# soldering.net
KiCad netlist of a schematic drawn in Altium Designer
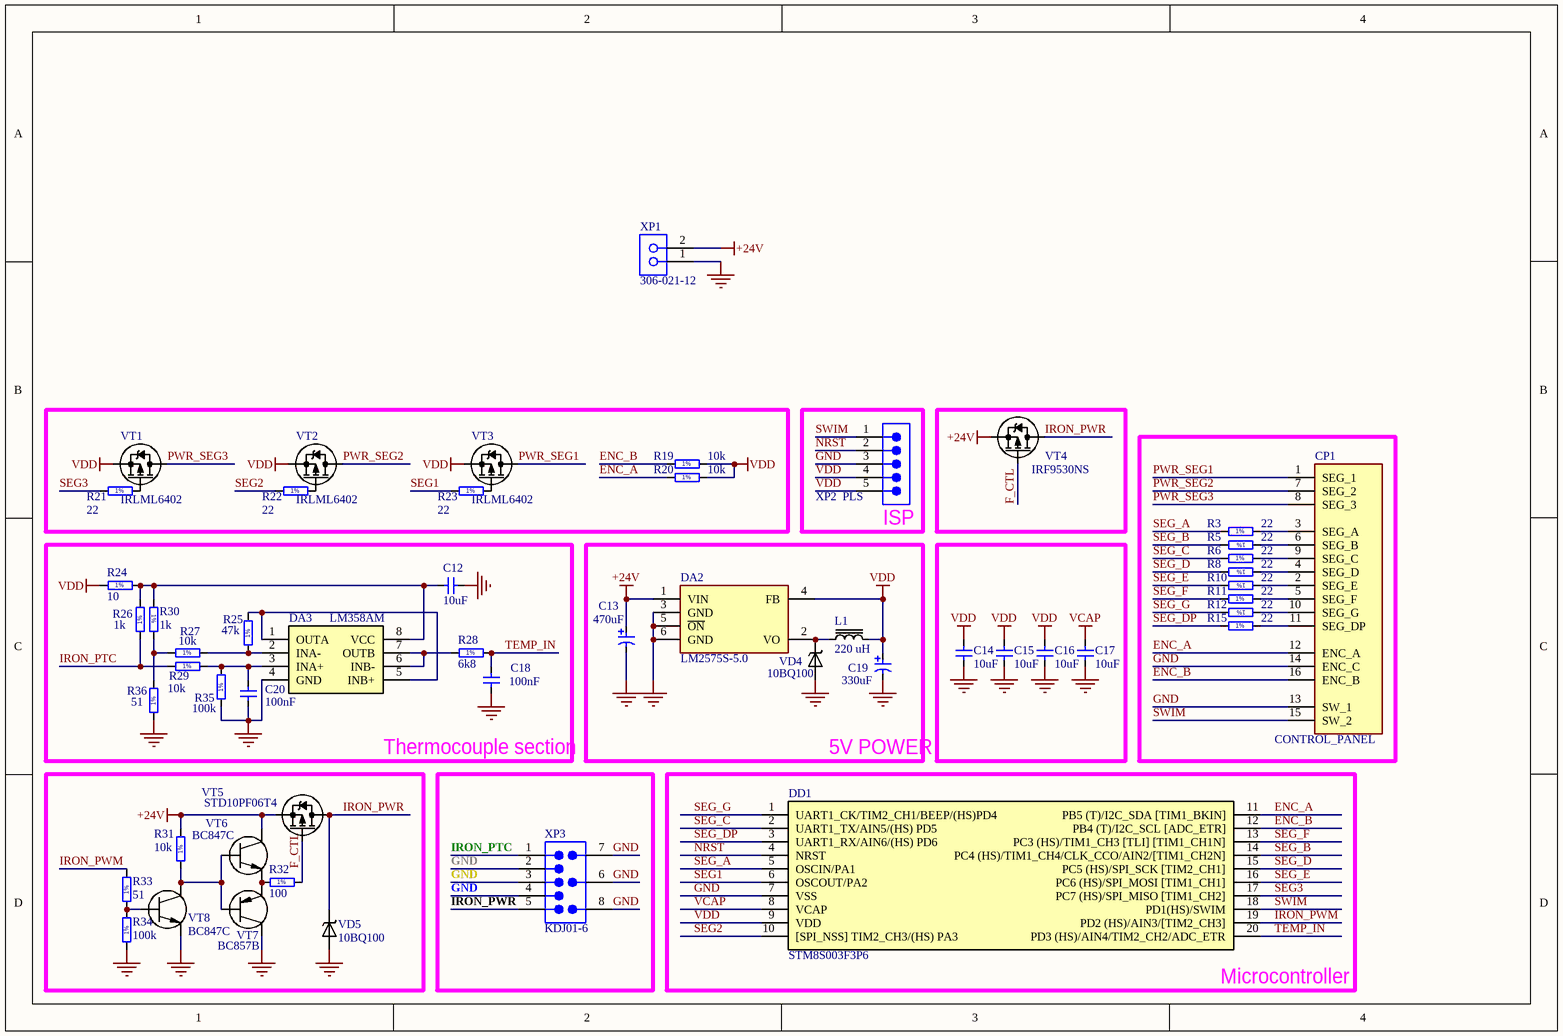
[diagram p0: soldering.SchDoc]

(export (version "E")
  (design (tool "Eeschema 10.0.6"))
  (components
    (comp (ref "C12")
      (value "10uF")
      (footprint "CAP0805R")
      (description "SMD 0805 Capacitor")
      (fields
        (field (name "PART NUMBER") "CC0805_10UF_10V_10%_X7R")
        (field (name "VOLTAGE") "10V")
        (field (name "AUTHOR") "I. Kuznetsov")
      )
      (libsource (lib "Capacitor") (part "CAP_NON_POLAR"))
    )
    (comp (ref "C13")
      (value "470uF")
      (footprint "CAP_EL_10_19_VERT")
      (fields (field (name "PART NUMBER") "SH050M0470B5S-1019 (VERT MOUNTED)") (field (name "VOLTAGE") "50V"))
      (libsource (lib "Capacitor") (part "CAP_POLAR"))
    )
    (comp (ref "C14")
      (value "10uF")
      (footprint "CAP0805R")
      (description "SMD 0805 Capacitor")
      (fields
        (field (name "PART NUMBER") "CC0805_10UF_10V_10%_X7R")
        (field (name "VOLTAGE") "10V")
        (field (name "AUTHOR") "I. Kuznetsov")
      )
      (libsource (lib "Capacitor") (part "CAP_NON_POLAR"))
    )
    (comp (ref "C15")
      (value "10uF")
      (footprint "CAP0805R")
      (description "SMD 0805 Capacitor")
      (fields
        (field (name "PART NUMBER") "CC0805_10UF_10V_10%_X7R")
        (field (name "VOLTAGE") "10V")
        (field (name "AUTHOR") "I. Kuznetsov")
      )
      (libsource (lib "Capacitor") (part "CAP_NON_POLAR"))
    )
    (comp (ref "C16")
      (value "10uF")
      (footprint "CAP0805R")
      (description "SMD 0805 Capacitor")
      (fields
        (field (name "PART NUMBER") "CC0805_10UF_10V_10%_X7R")
        (field (name "VOLTAGE") "10V")
        (field (name "AUTHOR") "I. Kuznetsov")
      )
      (libsource (lib "Capacitor") (part "CAP_NON_POLAR"))
    )
    (comp (ref "C17")
      (value "10uF")
      (footprint "CAP0805R")
      (description "SMD 0805 Capacitor")
      (fields
        (field (name "PART NUMBER") "CC0805_10UF_10V_10%_X7R")
        (field (name "VOLTAGE") "10V")
        (field (name "AUTHOR") "I. Kuznetsov")
      )
      (libsource (lib "Capacitor") (part "CAP_NON_POLAR"))
    )
    (comp (ref "C18")
      (value "100nF")
      (footprint "CAP0805R")
      (description "SMD 0805 Capacitor")
      (fields
        (field (name "PART NUMBER") "CC0805_100NF_50V_10%_X7R")
        (field (name "VOLTAGE") "50V")
        (field (name "AUTHOR") "I. Kuznetsov")
      )
      (libsource (lib "Capacitor") (part "CAP_NON_POLAR"))
    )
    (comp (ref "C19")
      (value "330uF")
      (footprint "TAN_D")
      (fields (field (name "PART NUMBER") "T495D337M010AHE100") (field (name "VOLTAGE") "10V"))
      (libsource (lib "Capacitor") (part "CAP_POLAR"))
    )
    (comp (ref "C20")
      (value "100nF")
      (footprint "CAP0805R")
      (description "SMD 0805 Capacitor")
      (fields
        (field (name "PART NUMBER") "CC0805_100NF_50V_10%_X7R")
        (field (name "VOLTAGE") "50V")
        (field (name "AUTHOR") "I. Kuznetsov")
      )
      (libsource (lib "Capacitor") (part "CAP_NON_POLAR"))
    )
    (comp (ref "CP1")
      (value "CONTROL_PANEL")
      (footprint "CONTROL_PANEL")
      (libsource (lib "soldering") (part "CONTROL_PANEL"))
    )
    (comp (ref "DA2")
      (value "LM2575S-5.0")
      (footprint "TO-263-5")
      (fields (field (name "MANUFACTURER") "TI") (field (name "AUTHOR") "I. Kuznetsov"))
      (libsource (lib "IC And Semiconductor") (part "LM2575S"))
    )
    (comp (ref "DA3")
      (value "OP Amp")
      (footprint "SOP8")
      (fields (field (name "PARTNUMBER") "LM358AM"))
      (libsource (lib "tonometr") (part "LM358AM"))
    )
    (comp (ref "DD1")
      (value "8 Bit MCU")
      (footprint "TSSOP20")
      (description "8 Bit MCU (STmicroelectronics)")
      (fields (field (name "PARTNUMBER") "STM8S003F3P6"))
      (libsource (lib "soldering") (part "STM8S003F3P6"))
    )
    (comp (ref "L1")
      (value "220 uH")
      (footprint "SL1016")
      (fields (field (name "PART NUMBER") "SL1016T-4R7K-B-N") (field (name "TOLERANCE") "± 10%"))
      (libsource (lib "Transformer") (part "Core_Inductor"))
    )
    (comp (ref "R3")
      (value "22")
      (footprint "RES0805R")
      (fields
        (field (name "PART NUMBER") "R0805_22R_1%_0.125W_100PPM")
        (field (name "POWER") "0.125W")
        (field (name "TOLERANCE") "±1%")
        (field (name "AUTHOR") "CERN DEM JLC")
      )
      (libsource (lib "Resistor") (part "Resistor - 1%"))
    )
    (comp (ref "R5")
      (value "22")
      (footprint "RES0805R")
      (fields
        (field (name "PART NUMBER") "R0805_22R_1%_0.125W_100PPM")
        (field (name "POWER") "0.125W")
        (field (name "TOLERANCE") "±1%")
        (field (name "AUTHOR") "CERN DEM JLC")
      )
      (libsource (lib "Resistor") (part "Resistor - 1%"))
    )
    (comp (ref "R6")
      (value "22")
      (footprint "RES0805R")
      (fields
        (field (name "PART NUMBER") "R0805_22R_1%_0.125W_100PPM")
        (field (name "POWER") "0.125W")
        (field (name "TOLERANCE") "±1%")
        (field (name "AUTHOR") "CERN DEM JLC")
      )
      (libsource (lib "Resistor") (part "Resistor - 1%"))
    )
    (comp (ref "R8")
      (value "22")
      (footprint "RES0805R")
      (fields
        (field (name "PART NUMBER") "R0805_22R_1%_0.125W_100PPM")
        (field (name "POWER") "0.125W")
        (field (name "TOLERANCE") "±1%")
        (field (name "AUTHOR") "CERN DEM JLC")
      )
      (libsource (lib "Resistor") (part "Resistor - 1%"))
    )
    (comp (ref "R10")
      (value "22")
      (footprint "RES0805R")
      (fields
        (field (name "PART NUMBER") "R0805_22R_1%_0.125W_100PPM")
        (field (name "POWER") "0.125W")
        (field (name "TOLERANCE") "±1%")
        (field (name "AUTHOR") "CERN DEM JLC")
      )
      (libsource (lib "Resistor") (part "Resistor - 1%"))
    )
    (comp (ref "R11")
      (value "22")
      (footprint "RES0805R")
      (fields
        (field (name "PART NUMBER") "R0805_22R_1%_0.125W_100PPM")
        (field (name "POWER") "0.125W")
        (field (name "TOLERANCE") "±1%")
        (field (name "AUTHOR") "CERN DEM JLC")
      )
      (libsource (lib "Resistor") (part "Resistor - 1%"))
    )
    (comp (ref "R12")
      (value "22")
      (footprint "RES0805R")
      (fields
        (field (name "PART NUMBER") "R0805_22R_1%_0.125W_100PPM")
        (field (name "POWER") "0.125W")
        (field (name "TOLERANCE") "±1%")
        (field (name "AUTHOR") "CERN DEM JLC")
      )
      (libsource (lib "Resistor") (part "Resistor - 1%"))
    )
    (comp (ref "R15")
      (value "22")
      (footprint "RES0805R")
      (fields
        (field (name "PART NUMBER") "R0805_22R_1%_0.125W_100PPM")
        (field (name "POWER") "0.125W")
        (field (name "TOLERANCE") "±1%")
        (field (name "AUTHOR") "CERN DEM JLC")
      )
      (libsource (lib "Resistor") (part "Resistor - 1%"))
    )
    (comp (ref "R19")
      (value "10k")
      (footprint "RES0805R")
      (fields
        (field (name "PART NUMBER") "R0805_10K_1%_0.125W_100PPM")
        (field (name "POWER") "0.125W")
        (field (name "TOLERANCE") "±1%")
        (field (name "AUTHOR") "CERN DEM JLC")
      )
      (libsource (lib "Resistor") (part "Resistor - 1%"))
    )
    (comp (ref "R20")
      (value "10k")
      (footprint "RES0805R")
      (fields
        (field (name "PART NUMBER") "R0805_10K_1%_0.125W_100PPM")
        (field (name "POWER") "0.125W")
        (field (name "TOLERANCE") "±1%")
        (field (name "AUTHOR") "CERN DEM JLC")
      )
      (libsource (lib "Resistor") (part "Resistor - 1%"))
    )
    (comp (ref "R21")
      (value "22")
      (footprint "RES0805R")
      (fields
        (field (name "PART NUMBER") "R0805_22R_1%_0.125W_100PPM")
        (field (name "POWER") "0.125W")
        (field (name "TOLERANCE") "±1%")
        (field (name "AUTHOR") "CERN DEM JLC")
      )
      (libsource (lib "Resistor") (part "Resistor - 1%"))
    )
    (comp (ref "R22")
      (value "22")
      (footprint "RES0805R")
      (fields
        (field (name "PART NUMBER") "R0805_22R_1%_0.125W_100PPM")
        (field (name "POWER") "0.125W")
        (field (name "TOLERANCE") "±1%")
        (field (name "AUTHOR") "CERN DEM JLC")
      )
      (libsource (lib "Resistor") (part "Resistor - 1%"))
    )
    (comp (ref "R23")
      (value "22")
      (footprint "RES0805R")
      (fields
        (field (name "PART NUMBER") "R0805_22R_1%_0.125W_100PPM")
        (field (name "POWER") "0.125W")
        (field (name "TOLERANCE") "±1%")
        (field (name "AUTHOR") "CERN DEM JLC")
      )
      (libsource (lib "Resistor") (part "Resistor - 1%"))
    )
    (comp (ref "R24")
      (value "10")
      (footprint "RES0805R")
      (fields
        (field (name "PART NUMBER") "R0805_10R_1%_0.125W_200PPM")
        (field (name "POWER") "0.125W")
        (field (name "TOLERANCE") "±1%")
        (field (name "AUTHOR") "CERN DEM JLC")
      )
      (libsource (lib "Resistor") (part "Resistor - 1%"))
    )
    (comp (ref "R25")
      (value "47k")
      (footprint "RES0805R")
      (fields
        (field (name "PART NUMBER") "R0805_47K_1%_0.125W_100PPM")
        (field (name "POWER") "0.125W")
        (field (name "TOLERANCE") "±1%")
        (field (name "AUTHOR") "CERN DEM JLC")
      )
      (libsource (lib "Resistor") (part "Resistor - 1%"))
    )
    (comp (ref "R26")
      (value "1k")
      (footprint "RES0805R")
      (fields
        (field (name "PART NUMBER") "R0805_1K_1%_0.125W_100PPM")
        (field (name "POWER") "0.125W")
        (field (name "TOLERANCE") "±1%")
        (field (name "AUTHOR") "CERN DEM JLC")
      )
      (libsource (lib "Resistor") (part "Resistor - 1%"))
    )
    (comp (ref "R27")
      (value "10k")
      (footprint "RES0805R")
      (fields
        (field (name "PART NUMBER") "R0805_10K_1%_0.125W_100PPM")
        (field (name "POWER") "0.125W")
        (field (name "TOLERANCE") "±1%")
        (field (name "AUTHOR") "CERN DEM JLC")
      )
      (libsource (lib "Resistor") (part "Resistor - 1%"))
    )
    (comp (ref "R28")
      (value "6k8")
      (footprint "RES0805R")
      (fields
        (field (name "PART NUMBER") "R0805_6K8_1%_0.125W_100PPM")
        (field (name "POWER") "0.125W")
        (field (name "TOLERANCE") "±1%")
        (field (name "AUTHOR") "CERN DEM JLC")
      )
      (libsource (lib "Resistor") (part "Resistor - 1%"))
    )
    (comp (ref "R29")
      (value "10k")
      (footprint "RES0805R")
      (fields
        (field (name "PART NUMBER") "R0805_10K_1%_0.125W_100PPM")
        (field (name "POWER") "0.125W")
        (field (name "TOLERANCE") "±1%")
        (field (name "AUTHOR") "CERN DEM JLC")
      )
      (libsource (lib "Resistor") (part "Resistor - 1%"))
    )
    (comp (ref "R30")
      (value "1k")
      (footprint "RES0805R")
      (fields
        (field (name "PART NUMBER") "R0805_1K_1%_0.125W_100PPM")
        (field (name "POWER") "0.125W")
        (field (name "TOLERANCE") "±1%")
        (field (name "AUTHOR") "CERN DEM JLC")
      )
      (libsource (lib "Resistor") (part "Resistor - 1%"))
    )
    (comp (ref "R31")
      (value "10k")
      (footprint "RES0805R")
      (fields
        (field (name "PART NUMBER") "R0805_10K_1%_0.125W_100PPM")
        (field (name "POWER") "0.125W")
        (field (name "TOLERANCE") "±1%")
        (field (name "AUTHOR") "CERN DEM JLC")
      )
      (libsource (lib "Resistor") (part "Resistor - 1%"))
    )
    (comp (ref "R32")
      (value "100")
      (footprint "RES0805R")
      (fields
        (field (name "PART NUMBER") "R0805_100R_1%_0.125W_100PPM")
        (field (name "POWER") "0.125W")
        (field (name "TOLERANCE") "±1%")
        (field (name "AUTHOR") "CERN DEM JLC")
      )
      (libsource (lib "Resistor") (part "Resistor - 1%"))
    )
    (comp (ref "R33")
      (value "51")
      (footprint "RES0805R")
      (fields
        (field (name "PART NUMBER") "R0805_51R_1%_0.125W_100PPM")
        (field (name "POWER") "0.125W")
        (field (name "TOLERANCE") "±1%")
        (field (name "AUTHOR") "CERN DEM JLC")
      )
      (libsource (lib "Resistor") (part "Resistor - 1%"))
    )
    (comp (ref "R34")
      (value "100k")
      (footprint "RES0805R")
      (fields
        (field (name "PART NUMBER") "R0805_100K_1%_0.125W_100PPM")
        (field (name "POWER") "0.125W")
        (field (name "TOLERANCE") "±1%")
        (field (name "AUTHOR") "CERN DEM JLC")
      )
      (libsource (lib "Resistor") (part "Resistor - 1%"))
    )
    (comp (ref "R35")
      (value "100k")
      (footprint "RES0805R")
      (fields
        (field (name "PART NUMBER") "R0805_100K_1%_0.125W_100PPM")
        (field (name "MANUFACTURER") "GENERIC")
        (field (name "MANUFACTURER1 PART NUMBER") "NRC10F1003TRF")
        (field (name "AUTHOR") "CERN DEM JLC")
      )
      (libsource (lib "Resistor") (part "Resistor - 1%"))
    )
    (comp (ref "R36")
      (value "51")
      (footprint "RES0805R")
      (fields
        (field (name "PART NUMBER") "R0805_51R_1%_0.125W_100PPM")
        (field (name "POWER") "0.125W")
        (field (name "TOLERANCE") "±1%")
        (field (name "AUTHOR") "CERN DEM JLC")
      )
      (libsource (lib "Resistor") (part "Resistor - 1%"))
    )
    (comp (ref "VD4")
      (value "10BQ100")
      (footprint "DO-214AA")
      (fields (field (name "MANUFACTURER") "IR") (field (name "AUTHOR") "I. Kuznetsov"))
      (libsource (lib "IC And Semiconductor") (part "Diode - Schottky"))
    )
    (comp (ref "VD5")
      (value "10BQ100")
      (footprint "DO-214AA")
      (fields (field (name "MANUFACTURER") "IR") (field (name "AUTHOR") "I. Kuznetsov"))
      (libsource (lib "IC And Semiconductor") (part "Diode - Schottky"))
    )
    (comp (ref "VT1")
      (value "IRLML6402")
      (footprint "SOT23")
      (fields (field (name "AUTHOR") "I. Kuznetsov"))
      (libsource (lib "IC And Semiconductor") (part "P_CH_MOSFET"))
    )
    (comp (ref "VT2")
      (value "IRLML6402")
      (footprint "SOT23")
      (fields (field (name "AUTHOR") "I. Kuznetsov"))
      (libsource (lib "IC And Semiconductor") (part "P_CH_MOSFET"))
    )
    (comp (ref "VT3")
      (value "IRLML6402")
      (footprint "SOT23")
      (fields (field (name "AUTHOR") "I. Kuznetsov"))
      (libsource (lib "IC And Semiconductor") (part "P_CH_MOSFET"))
    )
    (comp (ref "VT4")
      (value "IRF9530NS")
      (footprint "D2PAK")
      (libsource (lib "IC And Semiconductor") (part "P_CH_MOSFET"))
    )
    (comp (ref "VT5")
      (value "STD10PF06T4")
      (footprint "DPAK")
      (fields (field (name "AUTHOR") "I. Kuznetsov"))
      (libsource (lib "IC And Semiconductor") (part "P_CH_MOSFET"))
    )
    (comp (ref "VT6")
      (value "BC847C")
      (footprint "SOT23")
      (fields (field (name "AUTHOR") "I. Kuznetsov"))
      (libsource (lib "IC And Semiconductor") (part "NPN_BIPOLAR_SOT23"))
    )
    (comp (ref "VT7")
      (value "BC857B")
      (footprint "SOT23")
      (fields (field (name "AUTHOR") "I. Kuznetsov"))
      (libsource (lib "IC And Semiconductor") (part "PNP_BIPOLAR"))
    )
    (comp (ref "VT8")
      (value "BC847C")
      (footprint "SOT23")
      (fields (field (name "AUTHOR") "I. Kuznetsov"))
      (libsource (lib "IC And Semiconductor") (part "NPN_BIPOLAR_SOT23"))
    )
    (comp (ref "XP1")
      (value "306-021-12")
      (footprint "306-021-12")
      (libsource (lib "Connector") (part "CN_02S_1W"))
    )
    (comp (ref "XP2")
      (value "PLS")
      (footprint "PLS-05")
      (fields (field (name "PART NUMBER") "PLS-05") (field (name "MANUFACTURER") "AUK"))
      (libsource (lib "Connector") (part "CN_05P_1W"))
    )
    (comp (ref "XP3") (value "KDJ01-6") (footprint "KDJ01-6") (libsource (lib "Connector") (part "KDJ01-6")))
  )
  (nets
    (net (code "1") (name "+24V") (class "Default")
      (node (ref "C13") (pin "2") (pinfunction "2_2") (pintype "passive"))
      (node (ref "DA2") (pin "1") (pinfunction "VIN_1") (pintype "passive"))
      (node (ref "R31") (pin "2") (pinfunction "2_2") (pintype "passive"))
      (node (ref "VT4") (pin "2") (pinfunction "S_2") (pintype "passive"))
      (node (ref "VT5") (pin "2") (pinfunction "S_2") (pintype "passive"))
      (node (ref "VT6") (pin "3") (pinfunction "C_3") (pintype "passive"))
      (node (ref "XP1") (pin "2") (pinfunction "2_2") (pintype "passive"))
    )
    (net (code "2") (name "/ENC_A") (class "Default")
      (node (ref "CP1") (pin "12") (pinfunction "ENC_A_12") (pintype "passive"))
      (node (ref "DD1") (pin "11") (pinfunction "PB5_(T)/I2C_SDA_[TIM1_BKIN]_11") (pintype "passive"))
      (node (ref "R20") (pin "1") (pinfunction "1_1") (pintype "passive"))
    )
    (net (code "3") (name "/ENC_B") (class "Default")
      (node (ref "CP1") (pin "16") (pinfunction "ENC_B_16") (pintype "passive"))
      (node (ref "DD1") (pin "12") (pinfunction "PB4_(T)/I2C_SCL_[ADC_ETR]_12") (pintype "passive"))
      (node (ref "R19") (pin "1") (pinfunction "1_1") (pintype "passive"))
    )
    (net (code "4") (name "/F_CTL") (class "Default")
      (node (ref "R32") (pin "2") (pinfunction "2_2") (pintype "passive"))
      (node (ref "VT4") (pin "1") (pinfunction "G_1") (pintype "passive"))
      (node (ref "VT5") (pin "1") (pinfunction "G_1") (pintype "passive"))
    )
    (net (code "5") (name "/IRON_PTC") (class "Default")
      (node (ref "R26") (pin "1") (pinfunction "1_1") (pintype "passive"))
      (node (ref "R29") (pin "1") (pinfunction "1_1") (pintype "passive"))
      (node (ref "XP3") (pin "1") (pinfunction "1_1") (pintype "passive"))
    )
    (net (code "6") (name "/IRON_PWM") (class "Default")
      (node (ref "DD1") (pin "19") (pinfunction "PD2_(HS)/AIN3/[TIM2_CH3]_19") (pintype "passive"))
      (node (ref "R33") (pin "2") (pinfunction "2_2") (pintype "passive"))
    )
    (net (code "7") (name "/IRON_PWR") (class "Default")
      (node (ref "VD5") (pin "K") (pinfunction "K_K") (pintype "passive"))
      (node (ref "VT4") (pin "3") (pinfunction "D_3") (pintype "passive"))
      (node (ref "VT5") (pin "3") (pinfunction "D_3") (pintype "passive"))
      (node (ref "XP3") (pin "5") (pinfunction "5_5") (pintype "passive"))
    )
    (net (code "8") (name "/NRST") (class "Default")
      (node (ref "DD1") (pin "4") (pinfunction "NRST_4") (pintype "passive"))
      (node (ref "XP2") (pin "2") (pinfunction "2_2") (pintype "passive"))
    )
    (net (code "9") (name "/PWR_SEG1") (class "Default")
      (node (ref "CP1") (pin "1") (pinfunction "SEG_1_1") (pintype "passive"))
      (node (ref "VT3") (pin "3") (pinfunction "D_3") (pintype "passive"))
    )
    (net (code "10") (name "/PWR_SEG2") (class "Default")
      (node (ref "CP1") (pin "7") (pinfunction "SEG_2_7") (pintype "passive"))
      (node (ref "VT2") (pin "3") (pinfunction "D_3") (pintype "passive"))
    )
    (net (code "11") (name "/PWR_SEG3") (class "Default")
      (node (ref "CP1") (pin "8") (pinfunction "SEG_3_8") (pintype "passive"))
      (node (ref "VT1") (pin "3") (pinfunction "D_3") (pintype "passive"))
    )
    (net (code "12") (name "/SEG1") (class "Default")
      (node (ref "DD1") (pin "6") (pinfunction "OSCOUT/PA2_6") (pintype "passive"))
      (node (ref "R23") (pin "1") (pinfunction "1_1") (pintype "passive"))
    )
    (net (code "13") (name "/SEG2") (class "Default")
      (node (ref "DD1") (pin "10") (pinfunction "[SPI_NSS]_TIM2_CH3/(HS)_PA3_10") (pintype "passive"))
      (node (ref "R22") (pin "1") (pinfunction "1_1") (pintype "passive"))
    )
    (net (code "14") (name "/SEG3") (class "Default")
      (node (ref "DD1") (pin "17") (pinfunction "PC7_(HS)/SPI_MISO_[TIM1_CH2]_17") (pintype "passive"))
      (node (ref "R21") (pin "1") (pinfunction "1_1") (pintype "passive"))
    )
    (net (code "15") (name "/SEG_A") (class "Default")
      (node (ref "DD1") (pin "5") (pinfunction "OSCIN/PA1_5") (pintype "passive"))
      (node (ref "R3") (pin "1") (pinfunction "1_1") (pintype "passive"))
    )
    (net (code "16") (name "/SEG_B") (class "Default")
      (node (ref "DD1") (pin "14") (pinfunction "PC4_(HS)/TIM1_CH4/CLK_CCO/AIN2/[TIM1_CH2N]_14") (pintype "passive"))
      (node (ref "R5") (pin "2") (pinfunction "2_2") (pintype "passive"))
    )
    (net (code "17") (name "/SEG_C") (class "Default")
      (node (ref "DD1") (pin "2") (pinfunction "UART1_TX/AIN5/(HS)_PD5_2") (pintype "passive"))
      (node (ref "R6") (pin "1") (pinfunction "1_1") (pintype "passive"))
    )
    (net (code "18") (name "/SEG_D") (class "Default")
      (node (ref "DD1") (pin "15") (pinfunction "PC5_(HS)/SPI_SCK_[TIM2_CH1]_15") (pintype "passive"))
      (node (ref "R8") (pin "2") (pinfunction "2_2") (pintype "passive"))
    )
    (net (code "19") (name "/SEG_DP") (class "Default")
      (node (ref "DD1") (pin "3") (pinfunction "UART1_RX/AIN6/(HS)_PD6_3") (pintype "passive"))
      (node (ref "R15") (pin "1") (pinfunction "1_1") (pintype "passive"))
    )
    (net (code "20") (name "/SEG_E") (class "Default")
      (node (ref "DD1") (pin "16") (pinfunction "PC6_(HS)/SPI_MOSI_[TIM1_CH1]_16") (pintype "passive"))
      (node (ref "R10") (pin "2") (pinfunction "2_2") (pintype "passive"))
    )
    (net (code "21") (name "/SEG_F") (class "Default")
      (node (ref "DD1") (pin "13") (pinfunction "PC3_(HS)/TIM1_CH3_[TLI]_[TIM1_CH1N]_13") (pintype "passive"))
      (node (ref "R11") (pin "1") (pinfunction "1_1") (pintype "passive"))
    )
    (net (code "22") (name "/SEG_G") (class "Default")
      (node (ref "DD1") (pin "1") (pinfunction "UART1_CK/TIM2_CH1/BEEP/(HS)PD4_1") (pintype "passive"))
      (node (ref "R12") (pin "2") (pinfunction "2_2") (pintype "passive"))
    )
    (net (code "23") (name "/SWIM") (class "Default")
      (node (ref "CP1") (pin "15") (pinfunction "SW_2_15") (pintype "passive"))
      (node (ref "DD1") (pin "18") (pinfunction "PD1(HS)/SWIM_18") (pintype "passive"))
      (node (ref "XP2") (pin "1") (pinfunction "1_1") (pintype "passive"))
    )
    (net (code "24") (name "/TEMP_IN") (class "Default")
      (node (ref "C18") (pin "2") (pinfunction "2_2") (pintype "passive"))
      (node (ref "DD1") (pin "20") (pinfunction "PD3_(HS)/AIN4/TIM2_CH2/ADC_ETR_20") (pintype "passive"))
      (node (ref "R28") (pin "2") (pinfunction "2_2") (pintype "passive"))
    )
    (net (code "25") (name "GND") (class "Default")
      (node (ref "C12") (pin "2") (pinfunction "2_2") (pintype "passive"))
      (node (ref "C13") (pin "1") (pinfunction "1_1") (pintype "passive"))
      (node (ref "C14") (pin "1") (pinfunction "1_1") (pintype "passive"))
      (node (ref "C15") (pin "1") (pinfunction "1_1") (pintype "passive"))
      (node (ref "C16") (pin "1") (pinfunction "1_1") (pintype "passive"))
      (node (ref "C17") (pin "1") (pinfunction "1_1") (pintype "passive"))
      (node (ref "C18") (pin "1") (pinfunction "1_1") (pintype "passive"))
      (node (ref "C19") (pin "1") (pinfunction "1_1") (pintype "passive"))
      (node (ref "C20") (pin "1") (pinfunction "1_1") (pintype "passive"))
      (node (ref "CP1") (pin "13") (pinfunction "SW_1_13") (pintype "passive"))
      (node (ref "CP1") (pin "14") (pinfunction "ENC_C_14") (pintype "passive"))
      (node (ref "DA2") (pin "3") (pinfunction "GND_3") (pintype "passive"))
      (node (ref "DA2") (pin "5") (pinfunction "~{ON}_5") (pintype "passive"))
      (node (ref "DA2") (pin "6") (pinfunction "GND_6") (pintype "passive"))
      (node (ref "DA3") (pin "4") (pinfunction "GND_4") (pintype "passive"))
      (node (ref "DD1") (pin "7") (pinfunction "VSS_7") (pintype "passive"))
      (node (ref "R34") (pin "1") (pinfunction "1_1") (pintype "passive"))
      (node (ref "R35") (pin "1") (pinfunction "1_1") (pintype "passive"))
      (node (ref "R36") (pin "1") (pinfunction "1_1") (pintype "passive"))
      (node (ref "VD4") (pin "A") (pinfunction "A_A") (pintype "passive"))
      (node (ref "VD5") (pin "A") (pinfunction "A_A") (pintype "passive"))
      (node (ref "VT7") (pin "3") (pinfunction "C_3") (pintype "passive"))
      (node (ref "VT8") (pin "2") (pinfunction "E_2") (pintype "passive"))
      (node (ref "XP1") (pin "1") (pinfunction "1_1") (pintype "passive"))
      (node (ref "XP2") (pin "3") (pinfunction "3_3") (pintype "passive"))
      (node (ref "XP3") (pin "2") (pinfunction "2_2") (pintype "passive"))
      (node (ref "XP3") (pin "3") (pinfunction "3_3") (pintype "passive"))
      (node (ref "XP3") (pin "4") (pinfunction "4_4") (pintype "passive"))
      (node (ref "XP3") (pin "6") (pinfunction "6_6") (pintype "passive"))
      (node (ref "XP3") (pin "7") (pinfunction "7_7") (pintype "passive"))
      (node (ref "XP3") (pin "8") (pinfunction "8_8") (pintype "passive"))
    )
    (net (code "26") (name "Net-(CP1-SEG_A)") (class "Default")
      (node (ref "CP1") (pin "3") (pinfunction "SEG_A_3") (pintype "passive"))
      (node (ref "R3") (pin "2") (pinfunction "2_2") (pintype "passive"))
    )
    (net (code "27") (name "Net-(CP1-SEG_B)") (class "Default")
      (node (ref "CP1") (pin "6") (pinfunction "SEG_B_6") (pintype "passive"))
      (node (ref "R5") (pin "1") (pinfunction "1_1") (pintype "passive"))
    )
    (net (code "28") (name "Net-(CP1-SEG_C)") (class "Default")
      (node (ref "CP1") (pin "9") (pinfunction "SEG_C_9") (pintype "passive"))
      (node (ref "R6") (pin "2") (pinfunction "2_2") (pintype "passive"))
    )
    (net (code "29") (name "Net-(CP1-SEG_D)") (class "Default")
      (node (ref "CP1") (pin "4") (pinfunction "SEG_D_4") (pintype "passive"))
      (node (ref "R8") (pin "1") (pinfunction "1_1") (pintype "passive"))
    )
    (net (code "30") (name "Net-(CP1-SEG_DP)") (class "Default")
      (node (ref "CP1") (pin "11") (pinfunction "SEG_DP_11") (pintype "passive"))
      (node (ref "R15") (pin "2") (pinfunction "2_2") (pintype "passive"))
    )
    (net (code "31") (name "Net-(CP1-SEG_E)") (class "Default")
      (node (ref "CP1") (pin "2") (pinfunction "SEG_E_2") (pintype "passive"))
      (node (ref "R10") (pin "1") (pinfunction "1_1") (pintype "passive"))
    )
    (net (code "32") (name "Net-(CP1-SEG_F)") (class "Default")
      (node (ref "CP1") (pin "5") (pinfunction "SEG_F_5") (pintype "passive"))
      (node (ref "R11") (pin "2") (pinfunction "2_2") (pintype "passive"))
    )
    (net (code "33") (name "Net-(CP1-SEG_G)") (class "Default")
      (node (ref "CP1") (pin "10") (pinfunction "SEG_G_10") (pintype "passive"))
      (node (ref "R12") (pin "1") (pinfunction "1_1") (pintype "passive"))
    )
    (net (code "34") (name "Net-(DA2-VO)") (class "Default")
      (node (ref "DA2") (pin "2") (pinfunction "VO_2") (pintype "passive"))
      (node (ref "L1") (pin "1") (pinfunction "1_1") (pintype "passive"))
      (node (ref "VD4") (pin "K") (pinfunction "K_K") (pintype "passive"))
    )
    (net (code "35") (name "Net-(DA3-INA+)") (class "Default")
      (node (ref "C20") (pin "2") (pinfunction "2_2") (pintype "passive"))
      (node (ref "DA3") (pin "3") (pinfunction "INA+_3") (pintype "passive"))
      (node (ref "R29") (pin "2") (pinfunction "2_2") (pintype "passive"))
      (node (ref "R35") (pin "2") (pinfunction "2_2") (pintype "passive"))
    )
    (net (code "36") (name "Net-(DA3-INA-)") (class "Default")
      (node (ref "DA3") (pin "2") (pinfunction "INA-_2") (pintype "passive"))
      (node (ref "R25") (pin "1") (pinfunction "1_1") (pintype "passive"))
      (node (ref "R27") (pin "2") (pinfunction "2_2") (pintype "passive"))
    )
    (net (code "37") (name "Net-(DA3-INB+)") (class "Default")
      (node (ref "DA3") (pin "1") (pinfunction "OUTA_1") (pintype "passive"))
      (node (ref "DA3") (pin "5") (pinfunction "INB+_5") (pintype "passive"))
      (node (ref "R25") (pin "2") (pinfunction "2_2") (pintype "passive"))
    )
    (net (code "38") (name "Net-(DA3-INB-)") (class "Default")
      (node (ref "DA3") (pin "6") (pinfunction "INB-_6") (pintype "passive"))
      (node (ref "DA3") (pin "7") (pinfunction "OUTB_7") (pintype "passive"))
      (node (ref "R28") (pin "1") (pinfunction "1_1") (pintype "passive"))
    )
    (net (code "39") (name "Net-(DA3-VCC)") (class "Default")
      (node (ref "C12") (pin "1") (pinfunction "1_1") (pintype "passive"))
      (node (ref "DA3") (pin "8") (pinfunction "VCC_8") (pintype "passive"))
      (node (ref "R24") (pin "2") (pinfunction "2_2") (pintype "passive"))
      (node (ref "R26") (pin "2") (pinfunction "2_2") (pintype "passive"))
      (node (ref "R30") (pin "1") (pinfunction "1_1") (pintype "passive"))
    )
    (net (code "40") (name "Net-(R27-Pad1)") (class "Default")
      (node (ref "R27") (pin "1") (pinfunction "1_1") (pintype "passive"))
      (node (ref "R30") (pin "2") (pinfunction "2_2") (pintype "passive"))
      (node (ref "R36") (pin "2") (pinfunction "2_2") (pintype "passive"))
    )
    (net (code "41") (name "Net-(VT1-G)") (class "Default")
      (node (ref "R21") (pin "2") (pinfunction "2_2") (pintype "passive"))
      (node (ref "VT1") (pin "1") (pinfunction "G_1") (pintype "passive"))
    )
    (net (code "42") (name "Net-(VT2-G)") (class "Default")
      (node (ref "R22") (pin "2") (pinfunction "2_2") (pintype "passive"))
      (node (ref "VT2") (pin "1") (pinfunction "G_1") (pintype "passive"))
    )
    (net (code "43") (name "Net-(VT3-G)") (class "Default")
      (node (ref "R23") (pin "2") (pinfunction "2_2") (pintype "passive"))
      (node (ref "VT3") (pin "1") (pinfunction "G_1") (pintype "passive"))
    )
    (net (code "44") (name "Net-(VT6-B)") (class "Default")
      (node (ref "R31") (pin "1") (pinfunction "1_1") (pintype "passive"))
      (node (ref "VT6") (pin "1") (pinfunction "B_1") (pintype "passive"))
      (node (ref "VT7") (pin "1") (pinfunction "B_1") (pintype "passive"))
      (node (ref "VT8") (pin "3") (pinfunction "C_3") (pintype "passive"))
    )
    (net (code "45") (name "Net-(VT6-E)") (class "Default")
      (node (ref "R32") (pin "1") (pinfunction "1_1") (pintype "passive"))
      (node (ref "VT6") (pin "2") (pinfunction "E_2") (pintype "passive"))
      (node (ref "VT7") (pin "2") (pinfunction "E_2") (pintype "passive"))
    )
    (net (code "46") (name "Net-(VT8-B)") (class "Default")
      (node (ref "R33") (pin "1") (pinfunction "1_1") (pintype "passive"))
      (node (ref "R34") (pin "2") (pinfunction "2_2") (pintype "passive"))
      (node (ref "VT8") (pin "1") (pinfunction "B_1") (pintype "passive"))
    )
    (net (code "47") (name "VCAP") (class "Default")
      (node (ref "C17") (pin "2") (pinfunction "2_2") (pintype "passive"))
      (node (ref "DD1") (pin "8") (pinfunction "VCAP_8") (pintype "passive"))
    )
    (net (code "48") (name "VDD") (class "Default")
      (node (ref "C14") (pin "2") (pinfunction "2_2") (pintype "passive"))
      (node (ref "C15") (pin "2") (pinfunction "2_2") (pintype "passive"))
      (node (ref "C16") (pin "2") (pinfunction "2_2") (pintype "passive"))
      (node (ref "C19") (pin "2") (pinfunction "2_2") (pintype "passive"))
      (node (ref "DA2") (pin "4") (pinfunction "FB_4") (pintype "passive"))
      (node (ref "DD1") (pin "9") (pinfunction "VDD_9") (pintype "passive"))
      (node (ref "L1") (pin "2") (pinfunction "2_2") (pintype "passive"))
      (node (ref "R19") (pin "2") (pinfunction "2_2") (pintype "passive"))
      (node (ref "R20") (pin "2") (pinfunction "2_2") (pintype "passive"))
      (node (ref "R24") (pin "1") (pinfunction "1_1") (pintype "passive"))
      (node (ref "VT1") (pin "2") (pinfunction "S_2") (pintype "passive"))
      (node (ref "VT2") (pin "2") (pinfunction "S_2") (pintype "passive"))
      (node (ref "VT3") (pin "2") (pinfunction "S_2") (pintype "passive"))
      (node (ref "XP2") (pin "4") (pinfunction "4_4") (pintype "passive"))
      (node (ref "XP2") (pin "5") (pinfunction "5_5") (pintype "passive"))
    )
  )
)
